# TASC_cells_board.net
KiCad netlist of a schematic drawn in EAGLE
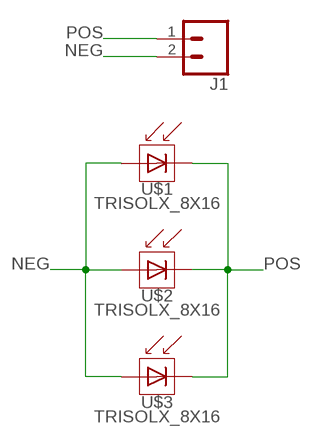
[diagram p0: schematic, sheet 1]

(export (version "E")
  (design (tool "Eeschema 10.0.6"))
  (components
    (comp (ref "J1")
      (value "CONN_02")
      (footprint "eagle-import:1X02")
      (libsource (lib "eagle-import") (part "CONN_02"))
    )
    (comp (ref "U$1")
      (value "TRISOLX_8X16")
      (footprint "eagle-import:TRISOLX_8X16")
      (libsource (lib "eagle-import") (part "TRISOLX_8X16"))
    )
    (comp (ref "U$2")
      (value "TRISOLX_8X16")
      (footprint "eagle-import:TRISOLX_8X16")
      (libsource (lib "eagle-import") (part "TRISOLX_8X16"))
    )
    (comp (ref "U$3")
      (value "TRISOLX_8X16")
      (footprint "eagle-import:TRISOLX_8X16")
      (libsource (lib "eagle-import") (part "TRISOLX_8X16"))
    )
  )
  (nets
    (net (code "1") (name "/NEG") (class "Default")
      (node (ref "J1") (pin "2") (pinfunction "2_2") (pintype "passive"))
      (node (ref "U$1") (pin "P$2") (pinfunction "A_P$2") (pintype "passive"))
      (node (ref "U$2") (pin "P$2") (pinfunction "A_P$2") (pintype "passive"))
      (node (ref "U$3") (pin "P$2") (pinfunction "A_P$2") (pintype "passive"))
    )
    (net (code "2") (name "/POS") (class "Default")
      (node (ref "J1") (pin "1") (pinfunction "1_1") (pintype "passive"))
      (node (ref "U$1") (pin "P$3") (pinfunction "C_P$3") (pintype "passive"))
      (node (ref "U$2") (pin "P$3") (pinfunction "C_P$3") (pintype "passive"))
      (node (ref "U$3") (pin "P$3") (pinfunction "C_P$3") (pintype "passive"))
    )
  )
)
